# RK3566_POWER.net
KiCad netlist of a schematic drawn in Altium Designer
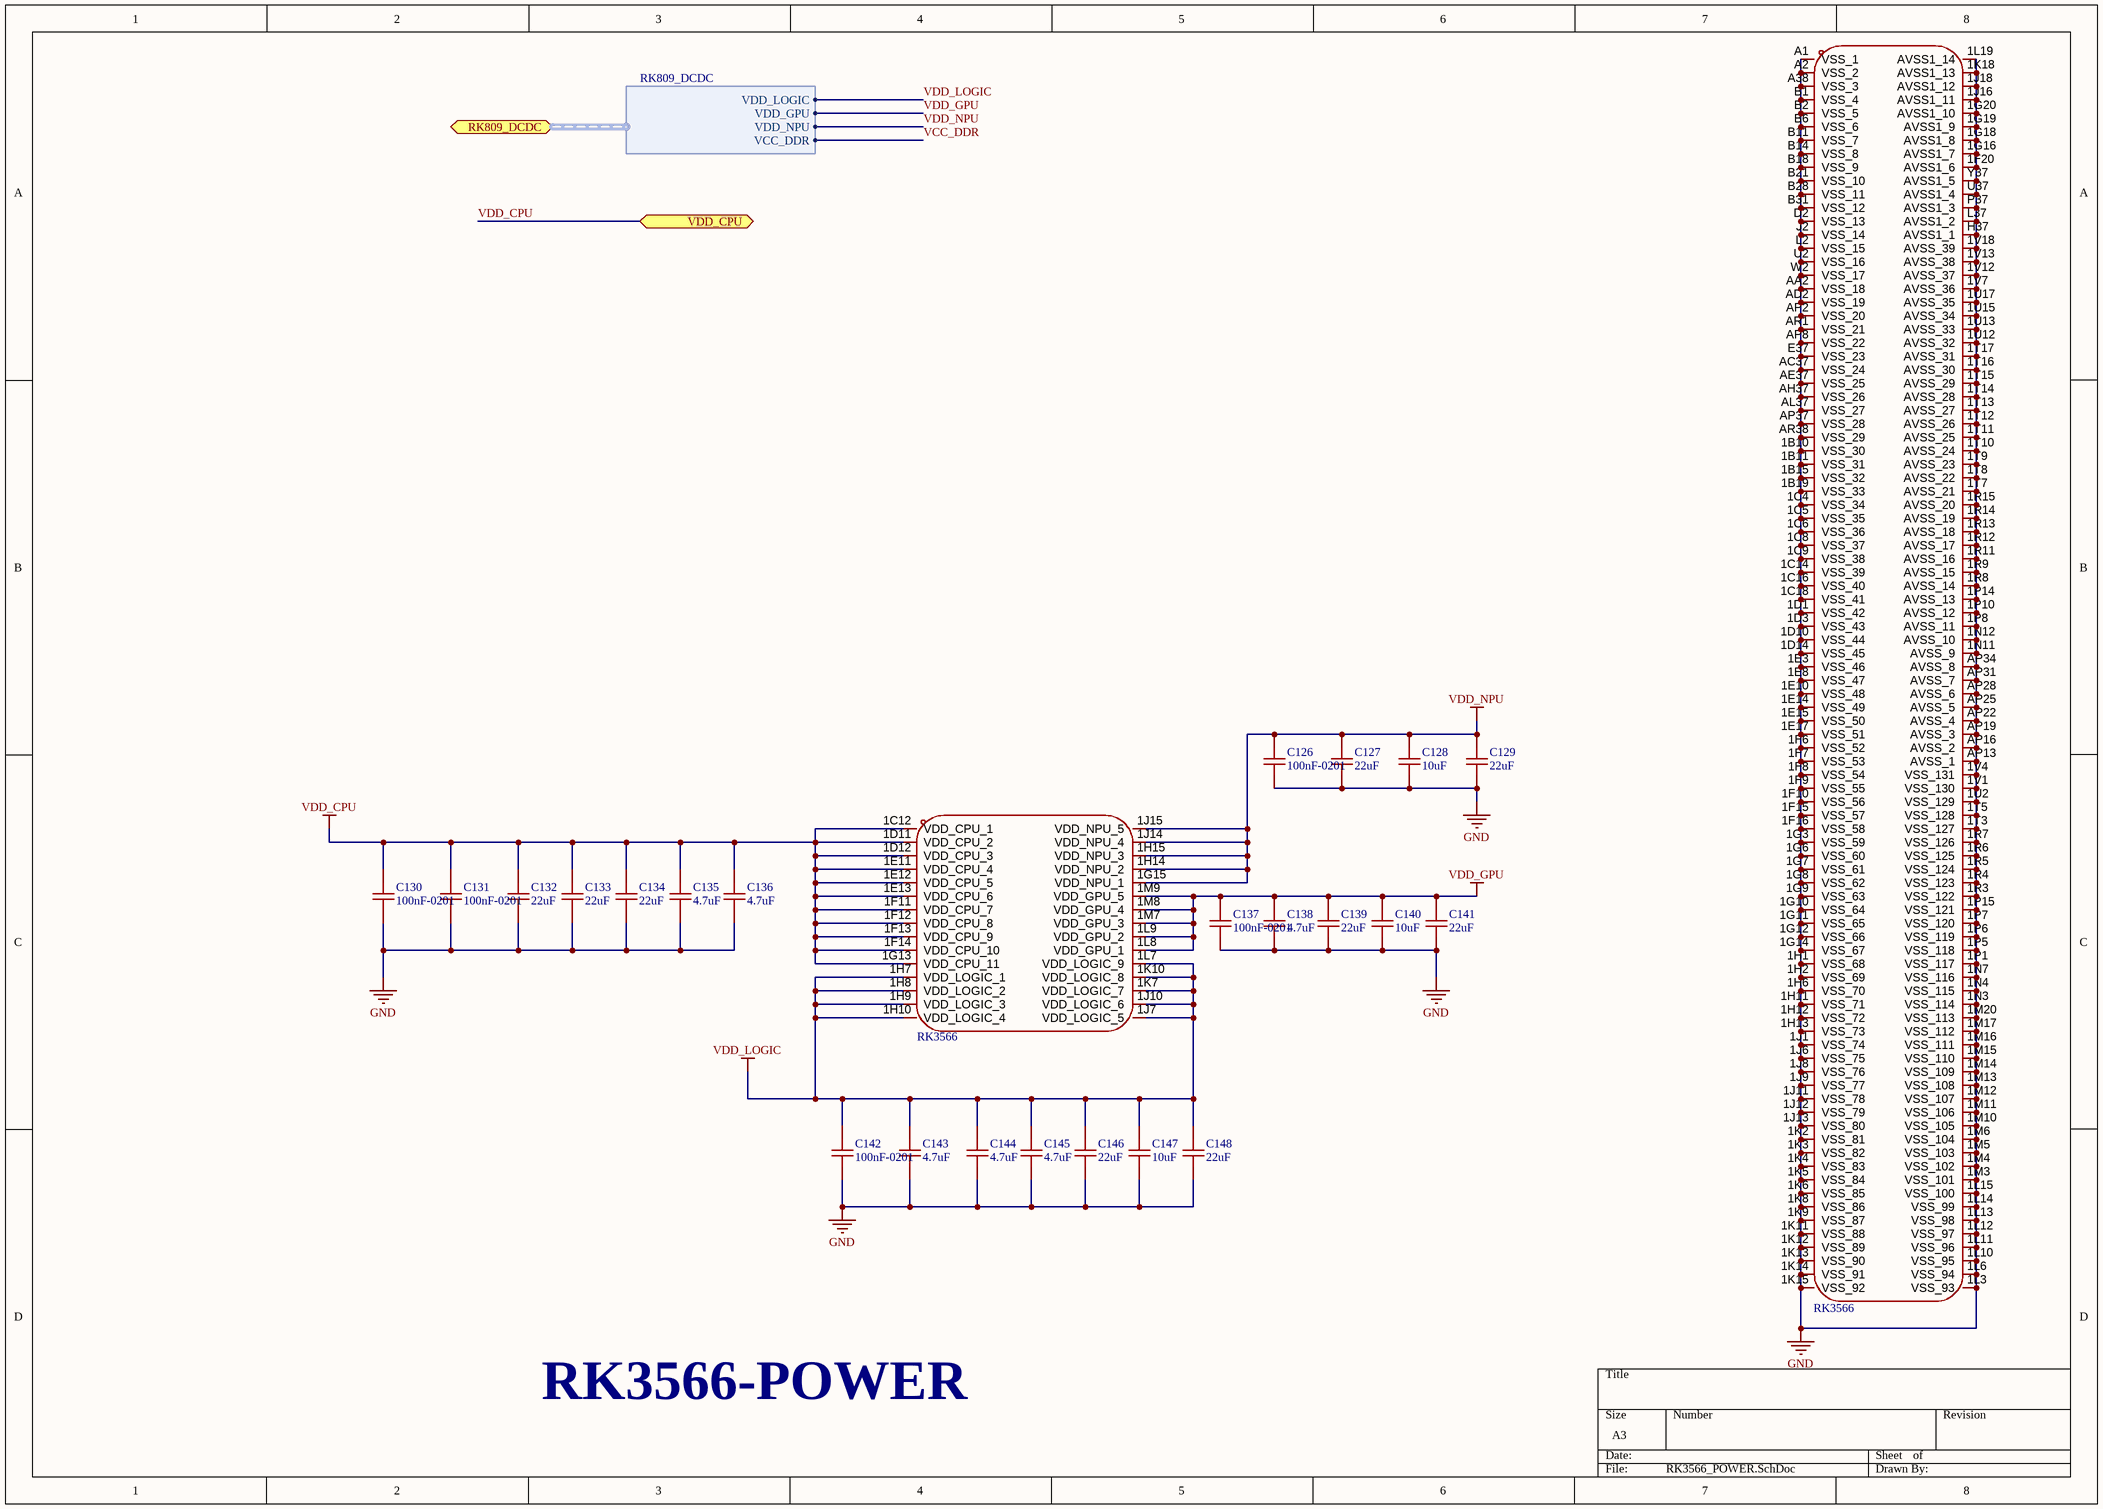
[diagram p0: RK3566_POWER.SchDoc]

(export (version "E")
  (design (tool "Eeschema 10.0.6"))
  (components
    (comp (ref "C126")
      (value "100nF-0201")
      (footprint "C0201")
      (description "CL03A104KO3NNNC")
      (libsource (lib "RLC") (part "100nF-0201"))
    )
    (comp (ref "C127")
      (value "22uF")
      (footprint "C0603")
      (description "16V 22uF X5R ±20% 0603 Ceramic Capacitors ROHS")
      (libsource (lib "RLC") (part "22uF"))
    )
    (comp (ref "C128")
      (value "10uF")
      (footprint "C0603")
      (description "10V 10uF X5R ±10% 0603 Ceramic Capacitors ROHS")
      (libsource (lib "RLC") (part "10uF"))
    )
    (comp (ref "C129")
      (value "22uF")
      (footprint "C0603")
      (description "16V 22uF X5R ±20% 0603 Ceramic Capacitors ROHS")
      (libsource (lib "RLC") (part "22uF"))
    )
    (comp (ref "C130")
      (value "100nF-0201")
      (footprint "C0201")
      (description "CL03A104KO3NNNC")
      (libsource (lib "RLC") (part "100nF-0201"))
    )
    (comp (ref "C131")
      (value "100nF-0201")
      (footprint "C0201")
      (description "CL03A104KO3NNNC")
      (libsource (lib "RLC") (part "100nF-0201"))
    )
    (comp (ref "C132")
      (value "22uF")
      (footprint "C0603")
      (description "16V 22uF X5R ±20% 0603 Ceramic Capacitors ROHS")
      (libsource (lib "RLC") (part "22uF"))
    )
    (comp (ref "C133")
      (value "22uF")
      (footprint "C0603")
      (description "16V 22uF X5R ±20% 0603 Ceramic Capacitors ROHS")
      (libsource (lib "RLC") (part "22uF"))
    )
    (comp (ref "C134")
      (value "22uF")
      (footprint "C0603")
      (description "16V 22uF X5R ±20% 0603 Ceramic Capacitors ROHS")
      (libsource (lib "RLC") (part "22uF"))
    )
    (comp (ref "C135")
      (value "4.7uF")
      (footprint "C0402")
      (description "10V 4.7uF X5R ±20% 0402 Ceramic Capacitors ROHS")
      (libsource (lib "RLC") (part "4.7uF"))
    )
    (comp (ref "C136")
      (value "4.7uF")
      (footprint "C0402")
      (description "10V 4.7uF X5R ±20% 0402 Ceramic Capacitors ROHS")
      (libsource (lib "RLC") (part "4.7uF"))
    )
    (comp (ref "C137")
      (value "100nF-0201")
      (footprint "C0201")
      (description "CL03A104KO3NNNC")
      (libsource (lib "RLC") (part "100nF-0201"))
    )
    (comp (ref "C138")
      (value "4.7uF")
      (footprint "C0402")
      (description "10V 4.7uF X5R ±20% 0402 Ceramic Capacitors ROHS")
      (libsource (lib "RLC") (part "4.7uF"))
    )
    (comp (ref "C139")
      (value "22uF")
      (footprint "C0603")
      (description "16V 22uF X5R ±20% 0603 Ceramic Capacitors ROHS")
      (libsource (lib "RLC") (part "22uF"))
    )
    (comp (ref "C140")
      (value "10uF")
      (footprint "C0603")
      (description "10V 10uF X5R ±10% 0603 Ceramic Capacitors ROHS")
      (libsource (lib "RLC") (part "10uF"))
    )
    (comp (ref "C141")
      (value "22uF")
      (footprint "C0603")
      (description "16V 22uF X5R ±20% 0603 Ceramic Capacitors ROHS")
      (libsource (lib "RLC") (part "22uF"))
    )
    (comp (ref "C142")
      (value "100nF-0201")
      (footprint "C0201")
      (description "CL03A104KO3NNNC")
      (libsource (lib "RLC") (part "100nF-0201"))
    )
    (comp (ref "C143")
      (value "4.7uF")
      (footprint "C0402")
      (description "10V 4.7uF X5R ±20% 0402 Ceramic Capacitors ROHS")
      (libsource (lib "RLC") (part "4.7uF"))
    )
    (comp (ref "C144")
      (value "4.7uF")
      (footprint "C0402")
      (description "10V 4.7uF X5R ±20% 0402 Ceramic Capacitors ROHS")
      (libsource (lib "RLC") (part "4.7uF"))
    )
    (comp (ref "C145")
      (value "4.7uF")
      (footprint "C0402")
      (description "10V 4.7uF X5R ±20% 0402 Ceramic Capacitors ROHS")
      (libsource (lib "RLC") (part "4.7uF"))
    )
    (comp (ref "C146")
      (value "22uF")
      (footprint "C0603")
      (description "16V 22uF X5R ±20% 0603 Ceramic Capacitors ROHS")
      (libsource (lib "RLC") (part "22uF"))
    )
    (comp (ref "C147")
      (value "10uF")
      (footprint "C0603")
      (description "10V 10uF X5R ±10% 0603 Ceramic Capacitors ROHS")
      (libsource (lib "RLC") (part "10uF"))
    )
    (comp (ref "C148")
      (value "22uF")
      (footprint "C0603")
      (description "16V 22uF X5R ±20% 0603 Ceramic Capacitors ROHS")
      (libsource (lib "RLC") (part "22uF"))
    )
    (comp (ref "U2")
      (value "RK3566")
      (footprint "BGA-565_L15.5-W14.4-P0.40_RK3566_1")
      (description "BGA-565(15.5x14.4)")
      (libsource (lib "IC") (part "RK3566"))
    )
  )
  (nets
    (net (code "4") (name "GND") (class "Default")
      (node (ref "C126") (pin "1") (pinfunction "1_1") (pintype "passive"))
      (node (ref "C127") (pin "1") (pinfunction "1_1") (pintype "passive"))
      (node (ref "C128") (pin "1") (pinfunction "1_1") (pintype "passive"))
      (node (ref "C129") (pin "1") (pinfunction "1_1") (pintype "passive"))
      (node (ref "C130") (pin "1") (pinfunction "1_1") (pintype "passive"))
      (node (ref "C131") (pin "1") (pinfunction "1_1") (pintype "passive"))
      (node (ref "C132") (pin "1") (pinfunction "1_1") (pintype "passive"))
      (node (ref "C133") (pin "1") (pinfunction "1_1") (pintype "passive"))
      (node (ref "C134") (pin "1") (pinfunction "1_1") (pintype "passive"))
      (node (ref "C135") (pin "1") (pinfunction "1_1") (pintype "passive"))
      (node (ref "C136") (pin "1") (pinfunction "1_1") (pintype "passive"))
      (node (ref "C137") (pin "1") (pinfunction "1_1") (pintype "passive"))
      (node (ref "C138") (pin "1") (pinfunction "1_1") (pintype "passive"))
      (node (ref "C139") (pin "1") (pinfunction "1_1") (pintype "passive"))
      (node (ref "C140") (pin "1") (pinfunction "1_1") (pintype "passive"))
      (node (ref "C141") (pin "1") (pinfunction "1_1") (pintype "passive"))
      (node (ref "C142") (pin "1") (pinfunction "1_1") (pintype "passive"))
      (node (ref "C143") (pin "1") (pinfunction "1_1") (pintype "passive"))
      (node (ref "C144") (pin "1") (pinfunction "1_1") (pintype "passive"))
      (node (ref "C145") (pin "1") (pinfunction "1_1") (pintype "passive"))
      (node (ref "C146") (pin "1") (pinfunction "1_1") (pintype "passive"))
      (node (ref "C147") (pin "1") (pinfunction "1_1") (pintype "passive"))
      (node (ref "C148") (pin "1") (pinfunction "1_1") (pintype "passive"))
      (node (ref "U2") (pin "1B10") (pinfunction "VSS_30_1B10") (pintype "passive"))
      (node (ref "U2") (pin "1B11") (pinfunction "VSS_31_1B11") (pintype "passive"))
      (node (ref "U2") (pin "1B15") (pinfunction "VSS_32_1B15") (pintype "passive"))
      (node (ref "U2") (pin "1B19") (pinfunction "VSS_33_1B19") (pintype "passive"))
      (node (ref "U2") (pin "1C14") (pinfunction "VSS_39_1C14") (pintype "passive"))
      (node (ref "U2") (pin "1C16") (pinfunction "VSS_40_1C16") (pintype "passive"))
      (node (ref "U2") (pin "1C18") (pinfunction "VSS_41_1C18") (pintype "passive"))
      (node (ref "U2") (pin "1C4") (pinfunction "VSS_34_1C4") (pintype "passive"))
      (node (ref "U2") (pin "1C5") (pinfunction "VSS_35_1C5") (pintype "passive"))
      (node (ref "U2") (pin "1C6") (pinfunction "VSS_36_1C6") (pintype "passive"))
      (node (ref "U2") (pin "1C8") (pinfunction "VSS_37_1C8") (pintype "passive"))
      (node (ref "U2") (pin "1C9") (pinfunction "VSS_38_1C9") (pintype "passive"))
      (node (ref "U2") (pin "1D1") (pinfunction "VSS_42_1D1") (pintype "passive"))
      (node (ref "U2") (pin "1D10") (pinfunction "VSS_44_1D10") (pintype "passive"))
      (node (ref "U2") (pin "1D14") (pinfunction "VSS_45_1D14") (pintype "passive"))
      (node (ref "U2") (pin "1D3") (pinfunction "VSS_43_1D3") (pintype "passive"))
      (node (ref "U2") (pin "1E10") (pinfunction "VSS_48_1E10") (pintype "passive"))
      (node (ref "U2") (pin "1E14") (pinfunction "VSS_49_1E14") (pintype "passive"))
      (node (ref "U2") (pin "1E15") (pinfunction "VSS_50_1E15") (pintype "passive"))
      (node (ref "U2") (pin "1E17") (pinfunction "VSS_51_1E17") (pintype "passive"))
      (node (ref "U2") (pin "1E3") (pinfunction "VSS_46_1E3") (pintype "passive"))
      (node (ref "U2") (pin "1E8") (pinfunction "VSS_47_1E8") (pintype "passive"))
      (node (ref "U2") (pin "1F10") (pinfunction "VSS_56_1F10") (pintype "passive"))
      (node (ref "U2") (pin "1F15") (pinfunction "VSS_57_1F15") (pintype "passive"))
      (node (ref "U2") (pin "1F16") (pinfunction "VSS_58_1F16") (pintype "passive"))
      (node (ref "U2") (pin "1F20") (pinfunction "AVSS1_6_1F20") (pintype "passive"))
      (node (ref "U2") (pin "1F6") (pinfunction "VSS_52_1F6") (pintype "passive"))
      (node (ref "U2") (pin "1F7") (pinfunction "VSS_53_1F7") (pintype "passive"))
      (node (ref "U2") (pin "1F8") (pinfunction "VSS_54_1F8") (pintype "passive"))
      (node (ref "U2") (pin "1F9") (pinfunction "VSS_55_1F9") (pintype "passive"))
      (node (ref "U2") (pin "1G10") (pinfunction "VSS_64_1G10") (pintype "passive"))
      (node (ref "U2") (pin "1G11") (pinfunction "VSS_65_1G11") (pintype "passive"))
      (node (ref "U2") (pin "1G12") (pinfunction "VSS_66_1G12") (pintype "passive"))
      (node (ref "U2") (pin "1G14") (pinfunction "VSS_67_1G14") (pintype "passive"))
      (node (ref "U2") (pin "1G16") (pinfunction "AVSS1_7_1G16") (pintype "passive"))
      (node (ref "U2") (pin "1G18") (pinfunction "AVSS1_8_1G18") (pintype "passive"))
      (node (ref "U2") (pin "1G19") (pinfunction "AVSS1_9_1G19") (pintype "passive"))
      (node (ref "U2") (pin "1G20") (pinfunction "AVSS1_10_1G20") (pintype "passive"))
      (node (ref "U2") (pin "1G3") (pinfunction "VSS_59_1G3") (pintype "passive"))
      (node (ref "U2") (pin "1G6") (pinfunction "VSS_60_1G6") (pintype "passive"))
      (node (ref "U2") (pin "1G7") (pinfunction "VSS_61_1G7") (pintype "passive"))
      (node (ref "U2") (pin "1G8") (pinfunction "VSS_62_1G8") (pintype "passive"))
      (node (ref "U2") (pin "1G9") (pinfunction "VSS_63_1G9") (pintype "passive"))
      (node (ref "U2") (pin "1H1") (pinfunction "VSS_68_1H1") (pintype "passive"))
      (node (ref "U2") (pin "1H11") (pinfunction "VSS_71_1H11") (pintype "passive"))
      (node (ref "U2") (pin "1H12") (pinfunction "VSS_72_1H12") (pintype "passive"))
      (node (ref "U2") (pin "1H13") (pinfunction "VSS_73_1H13") (pintype "passive"))
      (node (ref "U2") (pin "1H2") (pinfunction "VSS_69_1H2") (pintype "passive"))
      (node (ref "U2") (pin "1H6") (pinfunction "VSS_70_1H6") (pintype "passive"))
      (node (ref "U2") (pin "1J1") (pinfunction "VSS_74_1J1") (pintype "passive"))
      (node (ref "U2") (pin "1J11") (pinfunction "VSS_78_1J11") (pintype "passive"))
      (node (ref "U2") (pin "1J12") (pinfunction "VSS_79_1J12") (pintype "passive"))
      (node (ref "U2") (pin "1J13") (pinfunction "VSS_80_1J13") (pintype "passive"))
      (node (ref "U2") (pin "1J16") (pinfunction "AVSS1_11_1J16") (pintype "passive"))
      (node (ref "U2") (pin "1J18") (pinfunction "AVSS1_12_1J18") (pintype "passive"))
      (node (ref "U2") (pin "1J6") (pinfunction "VSS_75_1J6") (pintype "passive"))
      (node (ref "U2") (pin "1J8") (pinfunction "VSS_76_1J8") (pintype "passive"))
      (node (ref "U2") (pin "1J9") (pinfunction "VSS_77_1J9") (pintype "passive"))
      (node (ref "U2") (pin "1K11") (pinfunction "VSS_88_1K11") (pintype "passive"))
      (node (ref "U2") (pin "1K12") (pinfunction "VSS_89_1K12") (pintype "passive"))
      (node (ref "U2") (pin "1K13") (pinfunction "VSS_90_1K13") (pintype "passive"))
      (node (ref "U2") (pin "1K14") (pinfunction "VSS_91_1K14") (pintype "passive"))
      (node (ref "U2") (pin "1K15") (pinfunction "VSS_92_1K15") (pintype "passive"))
      (node (ref "U2") (pin "1K18") (pinfunction "AVSS1_13_1K18") (pintype "passive"))
      (node (ref "U2") (pin "1K2") (pinfunction "VSS_81_1K2") (pintype "passive"))
      (node (ref "U2") (pin "1K3") (pinfunction "VSS_82_1K3") (pintype "passive"))
      (node (ref "U2") (pin "1K4") (pinfunction "VSS_83_1K4") (pintype "passive"))
      (node (ref "U2") (pin "1K5") (pinfunction "VSS_84_1K5") (pintype "passive"))
      (node (ref "U2") (pin "1K6") (pinfunction "VSS_85_1K6") (pintype "passive"))
      (node (ref "U2") (pin "1K8") (pinfunction "VSS_86_1K8") (pintype "passive"))
      (node (ref "U2") (pin "1K9") (pinfunction "VSS_87_1K9") (pintype "passive"))
      (node (ref "U2") (pin "1L10") (pinfunction "VSS_95_1L10") (pintype "passive"))
      (node (ref "U2") (pin "1L11") (pinfunction "VSS_96_1L11") (pintype "passive"))
      (node (ref "U2") (pin "1L12") (pinfunction "VSS_97_1L12") (pintype "passive"))
      (node (ref "U2") (pin "1L13") (pinfunction "VSS_98_1L13") (pintype "passive"))
      (node (ref "U2") (pin "1L14") (pinfunction "VSS_99_1L14") (pintype "passive"))
      (node (ref "U2") (pin "1L15") (pinfunction "VSS_100_1L15") (pintype "passive"))
      (node (ref "U2") (pin "1L19") (pinfunction "AVSS1_14_1L19") (pintype "passive"))
      (node (ref "U2") (pin "1L3") (pinfunction "VSS_93_1L3") (pintype "passive"))
      (node (ref "U2") (pin "1L6") (pinfunction "VSS_94_1L6") (pintype "passive"))
      (node (ref "U2") (pin "1M10") (pinfunction "VSS_105_1M10") (pintype "passive"))
      (node (ref "U2") (pin "1M11") (pinfunction "VSS_106_1M11") (pintype "passive"))
      (node (ref "U2") (pin "1M12") (pinfunction "VSS_107_1M12") (pintype "passive"))
      (node (ref "U2") (pin "1M13") (pinfunction "VSS_108_1M13") (pintype "passive"))
      (node (ref "U2") (pin "1M14") (pinfunction "VSS_109_1M14") (pintype "passive"))
      (node (ref "U2") (pin "1M15") (pinfunction "VSS_110_1M15") (pintype "passive"))
      (node (ref "U2") (pin "1M16") (pinfunction "VSS_111_1M16") (pintype "passive"))
      (node (ref "U2") (pin "1M17") (pinfunction "VSS_112_1M17") (pintype "passive"))
      (node (ref "U2") (pin "1M20") (pinfunction "VSS_113_1M20") (pintype "passive"))
      (node (ref "U2") (pin "1M3") (pinfunction "VSS_101_1M3") (pintype "passive"))
      (node (ref "U2") (pin "1M4") (pinfunction "VSS_102_1M4") (pintype "passive"))
      (node (ref "U2") (pin "1M5") (pinfunction "VSS_103_1M5") (pintype "passive"))
      (node (ref "U2") (pin "1M6") (pinfunction "VSS_104_1M6") (pintype "passive"))
      (node (ref "U2") (pin "1N11") (pinfunction "AVSS_9_1N11") (pintype "passive"))
      (node (ref "U2") (pin "1N12") (pinfunction "AVSS_10_1N12") (pintype "passive"))
      (node (ref "U2") (pin "1N3") (pinfunction "VSS_114_1N3") (pintype "passive"))
      (node (ref "U2") (pin "1N4") (pinfunction "VSS_115_1N4") (pintype "passive"))
      (node (ref "U2") (pin "1N7") (pinfunction "VSS_116_1N7") (pintype "passive"))
      (node (ref "U2") (pin "1P1") (pinfunction "VSS_117_1P1") (pintype "passive"))
      (node (ref "U2") (pin "1P10") (pinfunction "AVSS_12_1P10") (pintype "passive"))
      (node (ref "U2") (pin "1P14") (pinfunction "AVSS_13_1P14") (pintype "passive"))
      (node (ref "U2") (pin "1P15") (pinfunction "VSS_121_1P15") (pintype "passive"))
      (node (ref "U2") (pin "1P5") (pinfunction "VSS_118_1P5") (pintype "passive"))
      (node (ref "U2") (pin "1P6") (pinfunction "VSS_119_1P6") (pintype "passive"))
      (node (ref "U2") (pin "1P7") (pinfunction "VSS_120_1P7") (pintype "passive"))
      (node (ref "U2") (pin "1P8") (pinfunction "AVSS_11_1P8") (pintype "passive"))
      (node (ref "U2") (pin "1R11") (pinfunction "AVSS_16_1R11") (pintype "passive"))
      (node (ref "U2") (pin "1R12") (pinfunction "AVSS_17_1R12") (pintype "passive"))
      (node (ref "U2") (pin "1R13") (pinfunction "AVSS_18_1R13") (pintype "passive"))
      (node (ref "U2") (pin "1R14") (pinfunction "AVSS_19_1R14") (pintype "passive"))
      (node (ref "U2") (pin "1R15") (pinfunction "AVSS_20_1R15") (pintype "passive"))
      (node (ref "U2") (pin "1R3") (pinfunction "VSS_122_1R3") (pintype "passive"))
      (node (ref "U2") (pin "1R4") (pinfunction "VSS_123_1R4") (pintype "passive"))
      (node (ref "U2") (pin "1R5") (pinfunction "VSS_124_1R5") (pintype "passive"))
      (node (ref "U2") (pin "1R6") (pinfunction "VSS_125_1R6") (pintype "passive"))
      (node (ref "U2") (pin "1R7") (pinfunction "VSS_126_1R7") (pintype "passive"))
      (node (ref "U2") (pin "1R8") (pinfunction "AVSS_14_1R8") (pintype "passive"))
      (node (ref "U2") (pin "1R9") (pinfunction "AVSS_15_1R9") (pintype "passive"))
      (node (ref "U2") (pin "1T10") (pinfunction "AVSS_24_1T10") (pintype "passive"))
      (node (ref "U2") (pin "1T11") (pinfunction "AVSS_25_1T11") (pintype "passive"))
      (node (ref "U2") (pin "1T12") (pinfunction "AVSS_26_1T12") (pintype "passive"))
      (node (ref "U2") (pin "1T13") (pinfunction "AVSS_27_1T13") (pintype "passive"))
      (node (ref "U2") (pin "1T14") (pinfunction "AVSS_28_1T14") (pintype "passive"))
      (node (ref "U2") (pin "1T15") (pinfunction "AVSS_29_1T15") (pintype "passive"))
      (node (ref "U2") (pin "1T16") (pinfunction "AVSS_30_1T16") (pintype "passive"))
      (node (ref "U2") (pin "1T17") (pinfunction "AVSS_31_1T17") (pintype "passive"))
      (node (ref "U2") (pin "1T3") (pinfunction "VSS_127_1T3") (pintype "passive"))
      (node (ref "U2") (pin "1T5") (pinfunction "VSS_128_1T5") (pintype "passive"))
      (node (ref "U2") (pin "1T7") (pinfunction "AVSS_21_1T7") (pintype "passive"))
      (node (ref "U2") (pin "1T8") (pinfunction "AVSS_22_1T8") (pintype "passive"))
      (node (ref "U2") (pin "1T9") (pinfunction "AVSS_23_1T9") (pintype "passive"))
      (node (ref "U2") (pin "1U12") (pinfunction "AVSS_32_1U12") (pintype "passive"))
      (node (ref "U2") (pin "1U13") (pinfunction "AVSS_33_1U13") (pintype "passive"))
      (node (ref "U2") (pin "1U15") (pinfunction "AVSS_34_1U15") (pintype "passive"))
      (node (ref "U2") (pin "1U17") (pinfunction "AVSS_35_1U17") (pintype "passive"))
      (node (ref "U2") (pin "1U2") (pinfunction "VSS_129_1U2") (pintype "passive"))
      (node (ref "U2") (pin "1V1") (pinfunction "VSS_130_1V1") (pintype "passive"))
      (node (ref "U2") (pin "1V12") (pinfunction "AVSS_37_1V12") (pintype "passive"))
      (node (ref "U2") (pin "1V13") (pinfunction "AVSS_38_1V13") (pintype "passive"))
      (node (ref "U2") (pin "1V18") (pinfunction "AVSS_39_1V18") (pintype "passive"))
      (node (ref "U2") (pin "1V4") (pinfunction "VSS_131_1V4") (pintype "passive"))
      (node (ref "U2") (pin "1V7") (pinfunction "AVSS_36_1V7") (pintype "passive"))
      (node (ref "U2") (pin "A1") (pinfunction "VSS_1_A1") (pintype "passive"))
      (node (ref "U2") (pin "A2") (pinfunction "VSS_2_A2") (pintype "passive"))
      (node (ref "U2") (pin "A38") (pinfunction "VSS_3_A38") (pintype "passive"))
      (node (ref "U2") (pin "AA2") (pinfunction "VSS_18_AA2") (pintype "passive"))
      (node (ref "U2") (pin "AC37") (pinfunction "VSS_24_AC37") (pintype "passive"))
      (node (ref "U2") (pin "AD2") (pinfunction "VSS_19_AD2") (pintype "passive"))
      (node (ref "U2") (pin "AE37") (pinfunction "VSS_25_AE37") (pintype "passive"))
      (node (ref "U2") (pin "AH37") (pinfunction "VSS_26_AH37") (pintype "passive"))
      (node (ref "U2") (pin "AL37") (pinfunction "VSS_27_AL37") (pintype "passive"))
      (node (ref "U2") (pin "AP13") (pinfunction "AVSS_1_AP13") (pintype "passive"))
      (node (ref "U2") (pin "AP16") (pinfunction "AVSS_2_AP16") (pintype "passive"))
      (node (ref "U2") (pin "AP19") (pinfunction "AVSS_3_AP19") (pintype "passive"))
      (node (ref "U2") (pin "AP2") (pinfunction "VSS_20_AP2") (pintype "passive"))
      (node (ref "U2") (pin "AP22") (pinfunction "AVSS_4_AP22") (pintype "passive"))
      (node (ref "U2") (pin "AP25") (pinfunction "AVSS_5_AP25") (pintype "passive"))
      (node (ref "U2") (pin "AP28") (pinfunction "AVSS_6_AP28") (pintype "passive"))
      (node (ref "U2") (pin "AP31") (pinfunction "AVSS_7_AP31") (pintype "passive"))
      (node (ref "U2") (pin "AP34") (pinfunction "AVSS_8_AP34") (pintype "passive"))
      (node (ref "U2") (pin "AP37") (pinfunction "VSS_28_AP37") (pintype "passive"))
      (node (ref "U2") (pin "AP8") (pinfunction "VSS_22_AP8") (pintype "passive"))
      (node (ref "U2") (pin "AR1") (pinfunction "VSS_21_AR1") (pintype "passive"))
      (node (ref "U2") (pin "AR38") (pinfunction "VSS_29_AR38") (pintype "passive"))
      (node (ref "U2") (pin "B1") (pinfunction "VSS_4_B1") (pintype "passive"))
      (node (ref "U2") (pin "B11") (pinfunction "VSS_7_B11") (pintype "passive"))
      (node (ref "U2") (pin "B14") (pinfunction "VSS_8_B14") (pintype "passive"))
      (node (ref "U2") (pin "B18") (pinfunction "VSS_9_B18") (pintype "passive"))
      (node (ref "U2") (pin "B2") (pinfunction "VSS_5_B2") (pintype "passive"))
      (node (ref "U2") (pin "B21") (pinfunction "VSS_10_B21") (pintype "passive"))
      (node (ref "U2") (pin "B28") (pinfunction "VSS_11_B28") (pintype "passive"))
      (node (ref "U2") (pin "B31") (pinfunction "VSS_12_B31") (pintype "passive"))
      (node (ref "U2") (pin "B6") (pinfunction "VSS_6_B6") (pintype "passive"))
      (node (ref "U2") (pin "D2") (pinfunction "VSS_13_D2") (pintype "passive"))
      (node (ref "U2") (pin "E37") (pinfunction "VSS_23_E37") (pintype "passive"))
      (node (ref "U2") (pin "H37") (pinfunction "AVSS1_1_H37") (pintype "passive"))
      (node (ref "U2") (pin "J2") (pinfunction "VSS_14_J2") (pintype "passive"))
      (node (ref "U2") (pin "L2") (pinfunction "VSS_15_L2") (pintype "passive"))
      (node (ref "U2") (pin "L37") (pinfunction "AVSS1_2_L37") (pintype "passive"))
      (node (ref "U2") (pin "P37") (pinfunction "AVSS1_3_P37") (pintype "passive"))
      (node (ref "U2") (pin "U2") (pinfunction "VSS_16_U2") (pintype "passive"))
      (node (ref "U2") (pin "U37") (pinfunction "AVSS1_4_U37") (pintype "passive"))
      (node (ref "U2") (pin "W2") (pinfunction "VSS_17_W2") (pintype "passive"))
      (node (ref "U2") (pin "Y37") (pinfunction "AVSS1_5_Y37") (pintype "passive"))
    )
    (net (code "5") (name "VDD_CPU") (class "Default")
      (node (ref "C130") (pin "2") (pinfunction "2_2") (pintype "passive"))
      (node (ref "C131") (pin "2") (pinfunction "2_2") (pintype "passive"))
      (node (ref "C132") (pin "2") (pinfunction "2_2") (pintype "passive"))
      (node (ref "C133") (pin "2") (pinfunction "2_2") (pintype "passive"))
      (node (ref "C134") (pin "2") (pinfunction "2_2") (pintype "passive"))
      (node (ref "C135") (pin "2") (pinfunction "2_2") (pintype "passive"))
      (node (ref "C136") (pin "2") (pinfunction "2_2") (pintype "passive"))
      (node (ref "U2") (pin "1C12") (pinfunction "VDD_CPU_1_1C12") (pintype "passive"))
      (node (ref "U2") (pin "1D11") (pinfunction "VDD_CPU_2_1D11") (pintype "passive"))
      (node (ref "U2") (pin "1D12") (pinfunction "VDD_CPU_3_1D12") (pintype "passive"))
      (node (ref "U2") (pin "1E11") (pinfunction "VDD_CPU_4_1E11") (pintype "passive"))
      (node (ref "U2") (pin "1E12") (pinfunction "VDD_CPU_5_1E12") (pintype "passive"))
      (node (ref "U2") (pin "1E13") (pinfunction "VDD_CPU_6_1E13") (pintype "passive"))
      (node (ref "U2") (pin "1F11") (pinfunction "VDD_CPU_7_1F11") (pintype "passive"))
      (node (ref "U2") (pin "1F12") (pinfunction "VDD_CPU_8_1F12") (pintype "passive"))
      (node (ref "U2") (pin "1F13") (pinfunction "VDD_CPU_9_1F13") (pintype "passive"))
      (node (ref "U2") (pin "1F14") (pinfunction "VDD_CPU_10_1F14") (pintype "passive"))
      (node (ref "U2") (pin "1G13") (pinfunction "VDD_CPU_11_1G13") (pintype "passive"))
    )
    (net (code "6") (name "VDD_GPU") (class "Default")
      (node (ref "C137") (pin "2") (pinfunction "2_2") (pintype "passive"))
      (node (ref "C138") (pin "2") (pinfunction "2_2") (pintype "passive"))
      (node (ref "C139") (pin "2") (pinfunction "2_2") (pintype "passive"))
      (node (ref "C140") (pin "2") (pinfunction "2_2") (pintype "passive"))
      (node (ref "C141") (pin "2") (pinfunction "2_2") (pintype "passive"))
      (node (ref "U2") (pin "1L8") (pinfunction "VDD_GPU_1_1L8") (pintype "passive"))
      (node (ref "U2") (pin "1L9") (pinfunction "VDD_GPU_2_1L9") (pintype "passive"))
      (node (ref "U2") (pin "1M7") (pinfunction "VDD_GPU_3_1M7") (pintype "passive"))
      (node (ref "U2") (pin "1M8") (pinfunction "VDD_GPU_4_1M8") (pintype "passive"))
      (node (ref "U2") (pin "1M9") (pinfunction "VDD_GPU_5_1M9") (pintype "passive"))
    )
    (net (code "7") (name "VDD_LOGIC") (class "Default")
      (node (ref "C142") (pin "2") (pinfunction "2_2") (pintype "passive"))
      (node (ref "C143") (pin "2") (pinfunction "2_2") (pintype "passive"))
      (node (ref "C144") (pin "2") (pinfunction "2_2") (pintype "passive"))
      (node (ref "C145") (pin "2") (pinfunction "2_2") (pintype "passive"))
      (node (ref "C146") (pin "2") (pinfunction "2_2") (pintype "passive"))
      (node (ref "C147") (pin "2") (pinfunction "2_2") (pintype "passive"))
      (node (ref "C148") (pin "2") (pinfunction "2_2") (pintype "passive"))
      (node (ref "U2") (pin "1H10") (pinfunction "VDD_LOGIC_4_1H10") (pintype "passive"))
      (node (ref "U2") (pin "1H7") (pinfunction "VDD_LOGIC_1_1H7") (pintype "passive"))
      (node (ref "U2") (pin "1H8") (pinfunction "VDD_LOGIC_2_1H8") (pintype "passive"))
      (node (ref "U2") (pin "1H9") (pinfunction "VDD_LOGIC_3_1H9") (pintype "passive"))
      (node (ref "U2") (pin "1J10") (pinfunction "VDD_LOGIC_6_1J10") (pintype "passive"))
      (node (ref "U2") (pin "1J7") (pinfunction "VDD_LOGIC_5_1J7") (pintype "passive"))
      (node (ref "U2") (pin "1K10") (pinfunction "VDD_LOGIC_8_1K10") (pintype "passive"))
      (node (ref "U2") (pin "1K7") (pinfunction "VDD_LOGIC_7_1K7") (pintype "passive"))
      (node (ref "U2") (pin "1L7") (pinfunction "VDD_LOGIC_9_1L7") (pintype "passive"))
    )
    (net (code "8") (name "VDD_NPU") (class "Default")
      (node (ref "C126") (pin "2") (pinfunction "2_2") (pintype "passive"))
      (node (ref "C127") (pin "2") (pinfunction "2_2") (pintype "passive"))
      (node (ref "C128") (pin "2") (pinfunction "2_2") (pintype "passive"))
      (node (ref "C129") (pin "2") (pinfunction "2_2") (pintype "passive"))
      (node (ref "U2") (pin "1G15") (pinfunction "VDD_NPU_1_1G15") (pintype "passive"))
      (node (ref "U2") (pin "1H14") (pinfunction "VDD_NPU_2_1H14") (pintype "passive"))
      (node (ref "U2") (pin "1H15") (pinfunction "VDD_NPU_3_1H15") (pintype "passive"))
      (node (ref "U2") (pin "1J14") (pinfunction "VDD_NPU_4_1J14") (pintype "passive"))
      (node (ref "U2") (pin "1J15") (pinfunction "VDD_NPU_5_1J15") (pintype "passive"))
    )
  )
)
